# STM32F4.net
KiCad netlist of a schematic drawn in Altium Designer
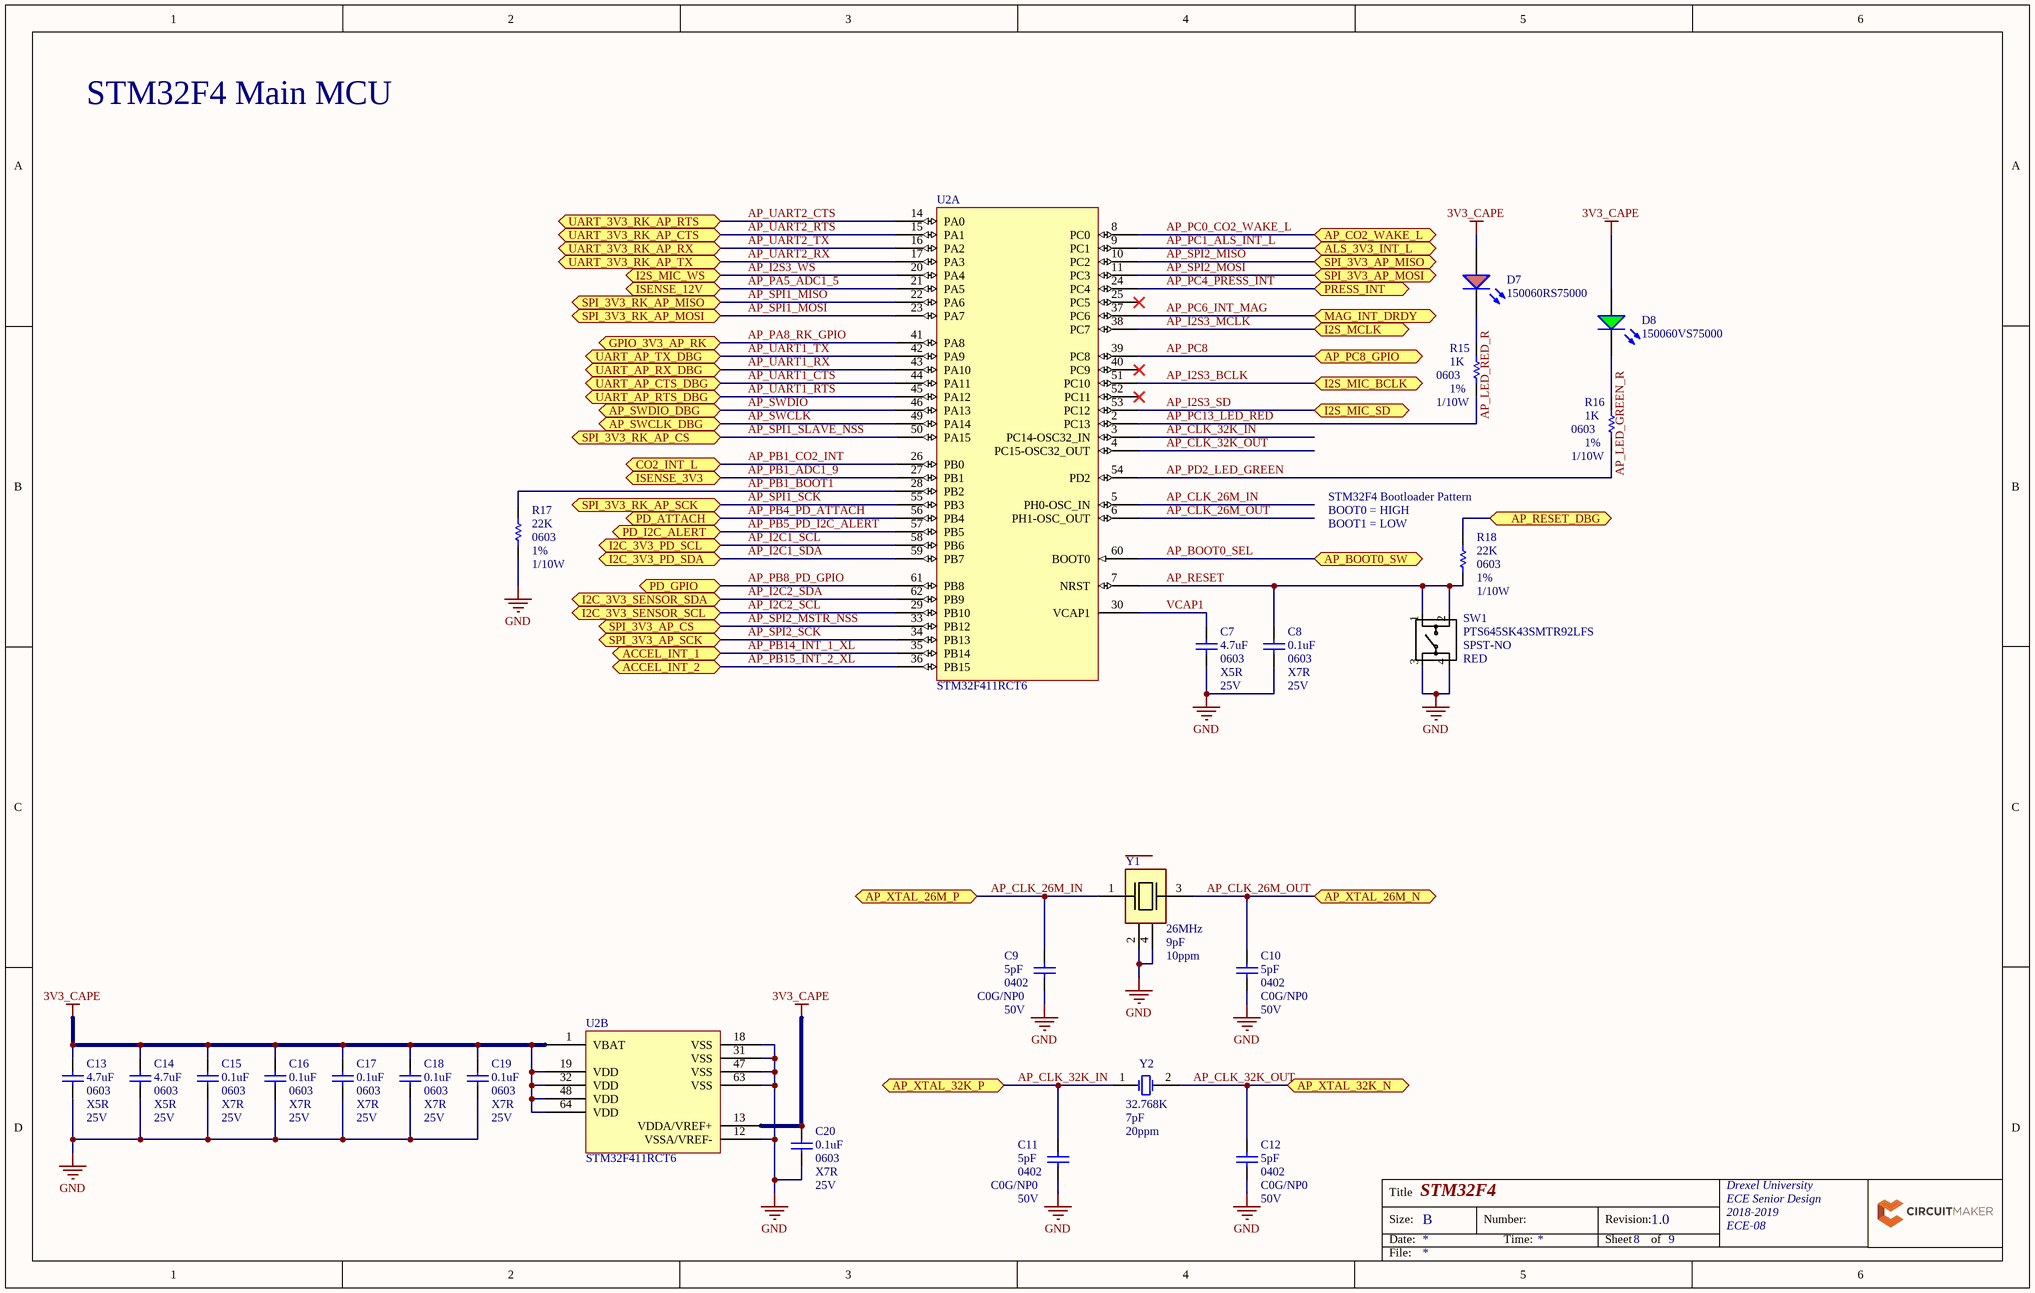
[diagram p0: STM32F4.SchDoc]

(export (version "E")
  (design (tool "Eeschema 10.0.6"))
  (components
    (comp (ref "C7")
      (value "Murata GRM188R61E475KE11D")
      (footprint "CAPC1608X90X35ML10T15")
      (description "CAP CER 4.7UF 25V 10% X5R 0603")
      (fields
        (field (name "CAPACITANCE") "4.7uF")
        (field (name "CASE/PACKAGE") "0603")
        (field (name "DIELECTRIC CHARACTERISTIC") "X5R")
        (field (name "VOLTAGE RATING (DC)") "25V")
        (field (name "MANUFACTURER PART NUMBER") "GRM188R61E475KE11D")
      )
      (libsource (lib "CommunityVault") (part "CMP-8856396-4"))
    )
    (comp (ref "C8")
      (value "Würth Elektronik 885012206071")
      (footprint "PCB-8usp83j76ntw2xroyu3n-1")
      (description "Multilayer Ceramic Capacitor, WCAP-CSGP Series, 0.1 F, 10%, X7R, 25 V, 0603 [1608 Metric]")
      (fields
        (field (name "DIELECTRIC CHARACTERISTIC") "X7R")
        (field (name "VOLTAGE RATING (DC)") "25V")
        (field (name "CAPACITANCE") "0.1uF")
        (field (name "MANUFACTURER PART NUMBER") "885012206071")
        (field (name "PACKAGE") "0603")
      )
      (libsource (lib "CommunityVault") (part "CMP-034ac9768ab0dc8d-1"))
    )
    (comp (ref "C9")
      (value "AVX Interconnect / Elco 04025A5R0CAT2A")
      (footprint "CAPC1005X56X25ML10T15")
      (description "Multilayer Ceramic Capacitors MLCC - SMD/SMT 0402 5pF 50volts C0G +/-0.25pF")
      (fields
        (field (name "CAPACITANCE") "5pF")
        (field (name "CASE/PACKAGE") "0402")
        (field (name "DIELECTRIC CHARACTERISTIC") "C0G/NP0")
        (field (name "VOLTAGE RATING (DC)") "50V")
        (field (name "MANUFACTURER PART NUMBER") "04025A5R0CAT2A")
      )
      (libsource (lib "CommunityVault") (part "CMP-173336-2"))
    )
    (comp (ref "C10")
      (value "AVX Interconnect / Elco 04025A5R0CAT2A")
      (footprint "CAPC1005X56X25ML10T15")
      (description "Multilayer Ceramic Capacitors MLCC - SMD/SMT 0402 5pF 50volts C0G +/-0.25pF")
      (fields
        (field (name "CAPACITANCE") "5pF")
        (field (name "CASE/PACKAGE") "0402")
        (field (name "DIELECTRIC CHARACTERISTIC") "C0G/NP0")
        (field (name "VOLTAGE RATING (DC)") "50V")
        (field (name "MANUFACTURER PART NUMBER") "04025A5R0CAT2A")
      )
      (libsource (lib "CommunityVault") (part "CMP-173336-2"))
    )
    (comp (ref "C11")
      (value "AVX Interconnect / Elco 04025A5R0CAT2A")
      (footprint "CAPC1005X56X25ML10T15")
      (description "Multilayer Ceramic Capacitors MLCC - SMD/SMT 0402 5pF 50volts C0G +/-0.25pF")
      (fields
        (field (name "CAPACITANCE") "5pF")
        (field (name "CASE/PACKAGE") "0402")
        (field (name "DIELECTRIC CHARACTERISTIC") "C0G/NP0")
        (field (name "VOLTAGE RATING (DC)") "50V")
        (field (name "MANUFACTURER PART NUMBER") "04025A5R0CAT2A")
      )
      (libsource (lib "CommunityVault") (part "CMP-173336-2"))
    )
    (comp (ref "C12")
      (value "AVX Interconnect / Elco 04025A5R0CAT2A")
      (footprint "CAPC1005X56X25ML10T15")
      (description "Multilayer Ceramic Capacitors MLCC - SMD/SMT 0402 5pF 50volts C0G +/-0.25pF")
      (fields
        (field (name "CAPACITANCE") "5pF")
        (field (name "CASE/PACKAGE") "0402")
        (field (name "DIELECTRIC CHARACTERISTIC") "C0G/NP0")
        (field (name "VOLTAGE RATING (DC)") "50V")
        (field (name "MANUFACTURER PART NUMBER") "04025A5R0CAT2A")
      )
      (libsource (lib "CommunityVault") (part "CMP-173336-2"))
    )
    (comp (ref "C13")
      (value "Murata GRM188R61E475KE11D")
      (footprint "CAPC1608X90X35ML10T15")
      (description "CAP CER 4.7UF 25V 10% X5R 0603")
      (fields
        (field (name "CAPACITANCE") "4.7uF")
        (field (name "CASE/PACKAGE") "0603")
        (field (name "DIELECTRIC CHARACTERISTIC") "X5R")
        (field (name "VOLTAGE RATING (DC)") "25V")
        (field (name "MANUFACTURER PART NUMBER") "GRM188R61E475KE11D")
      )
      (libsource (lib "CommunityVault") (part "CMP-8856396-4"))
    )
    (comp (ref "C14")
      (value "Murata GRM188R61E475KE11D")
      (footprint "CAPC1608X90X35ML10T15")
      (description "CAP CER 4.7UF 25V 10% X5R 0603")
      (fields
        (field (name "CAPACITANCE") "4.7uF")
        (field (name "CASE/PACKAGE") "0603")
        (field (name "DIELECTRIC CHARACTERISTIC") "X5R")
        (field (name "VOLTAGE RATING (DC)") "25V")
        (field (name "MANUFACTURER PART NUMBER") "GRM188R61E475KE11D")
      )
      (libsource (lib "CommunityVault") (part "CMP-8856396-4"))
    )
    (comp (ref "C15")
      (value "Würth Elektronik 885012206071")
      (footprint "PCB-8usp83j76ntw2xroyu3n-1")
      (description "Multilayer Ceramic Capacitor, WCAP-CSGP Series, 0.1 F, 10%, X7R, 25 V, 0603 [1608 Metric]")
      (fields
        (field (name "DIELECTRIC CHARACTERISTIC") "X7R")
        (field (name "VOLTAGE RATING (DC)") "25V")
        (field (name "CAPACITANCE") "0.1uF")
        (field (name "MANUFACTURER PART NUMBER") "885012206071")
        (field (name "PACKAGE") "0603")
      )
      (libsource (lib "CommunityVault") (part "CMP-034ac9768ab0dc8d-1"))
    )
    (comp (ref "C16")
      (value "Würth Elektronik 885012206071")
      (footprint "PCB-8usp83j76ntw2xroyu3n-1")
      (description "Multilayer Ceramic Capacitor, WCAP-CSGP Series, 0.1 F, 10%, X7R, 25 V, 0603 [1608 Metric]")
      (fields
        (field (name "DIELECTRIC CHARACTERISTIC") "X7R")
        (field (name "VOLTAGE RATING (DC)") "25V")
        (field (name "CAPACITANCE") "0.1uF")
        (field (name "MANUFACTURER PART NUMBER") "885012206071")
        (field (name "PACKAGE") "0603")
      )
      (libsource (lib "CommunityVault") (part "CMP-034ac9768ab0dc8d-1"))
    )
    (comp (ref "C17")
      (value "Würth Elektronik 885012206071")
      (footprint "PCB-8usp83j76ntw2xroyu3n-1")
      (description "Multilayer Ceramic Capacitor, WCAP-CSGP Series, 0.1 F, 10%, X7R, 25 V, 0603 [1608 Metric]")
      (fields
        (field (name "DIELECTRIC CHARACTERISTIC") "X7R")
        (field (name "VOLTAGE RATING (DC)") "25V")
        (field (name "CAPACITANCE") "0.1uF")
        (field (name "MANUFACTURER PART NUMBER") "885012206071")
        (field (name "PACKAGE") "0603")
      )
      (libsource (lib "CommunityVault") (part "CMP-034ac9768ab0dc8d-1"))
    )
    (comp (ref "C18")
      (value "Würth Elektronik 885012206071")
      (footprint "PCB-8usp83j76ntw2xroyu3n-1")
      (description "Multilayer Ceramic Capacitor, WCAP-CSGP Series, 0.1 F, 10%, X7R, 25 V, 0603 [1608 Metric]")
      (fields
        (field (name "DIELECTRIC CHARACTERISTIC") "X7R")
        (field (name "VOLTAGE RATING (DC)") "25V")
        (field (name "CAPACITANCE") "0.1uF")
        (field (name "MANUFACTURER PART NUMBER") "885012206071")
        (field (name "PACKAGE") "0603")
      )
      (libsource (lib "CommunityVault") (part "CMP-034ac9768ab0dc8d-1"))
    )
    (comp (ref "C19")
      (value "Würth Elektronik 885012206071")
      (footprint "PCB-8usp83j76ntw2xroyu3n-1")
      (description "Multilayer Ceramic Capacitor, WCAP-CSGP Series, 0.1 F, 10%, X7R, 25 V, 0603 [1608 Metric]")
      (fields
        (field (name "DIELECTRIC CHARACTERISTIC") "X7R")
        (field (name "VOLTAGE RATING (DC)") "25V")
        (field (name "CAPACITANCE") "0.1uF")
        (field (name "MANUFACTURER PART NUMBER") "885012206071")
        (field (name "PACKAGE") "0603")
      )
      (libsource (lib "CommunityVault") (part "CMP-034ac9768ab0dc8d-1"))
    )
    (comp (ref "C20")
      (value "Würth Elektronik 885012206071")
      (footprint "PCB-8usp83j76ntw2xroyu3n-1")
      (description "Multilayer Ceramic Capacitor, WCAP-CSGP Series, 0.1 F, 10%, X7R, 25 V, 0603 [1608 Metric]")
      (fields
        (field (name "DIELECTRIC CHARACTERISTIC") "X7R")
        (field (name "VOLTAGE RATING (DC)") "25V")
        (field (name "CAPACITANCE") "0.1uF")
        (field (name "MANUFACTURER PART NUMBER") "885012206071")
        (field (name "PACKAGE") "0603")
      )
      (libsource (lib "CommunityVault") (part "CMP-034ac9768ab0dc8d-1"))
    )
    (comp (ref "D7")
      (value "150060RS75000")
      (footprint "PCB-gaza7c7mdlgwi4y82xs2-1")
      (description "Standard LEDs - SMD WL-SMCW SMDMono TpVw Waterclr 0603 Red")
      (libsource (lib "CommunityVault") (part "SYM-47368ff9174098f1-2"))
    )
    (comp (ref "D8")
      (value "150060VS75000")
      (footprint "0603_A")
      (description "SMD mono-color Chip LED, WL-SMCW, Bright Green")
      (libsource (lib "FavoritesLibrary") (part "WE-LED_K1A2-2"))
    )
    (comp (ref "R15")
      (value "Stackpole Electronics RMCF0603FT1K00")
      (footprint "PCB-rzdzs5ckhrcob8ss0hvn-1")
      (description "RMCF Series 0603 0.1 W 1 kOhm ±1 % ±100 ppm/°C SMT Thick Film Chip Resistor")
      (fields
        (field (name "CASE/PACKAGE") "0603")
        (field (name "POWER RATING") "1/10W")
        (field (name "MANUFACTURER PART NUMBER") "RMCF0603FT1K00")
        (field (name "RESISTANCE") "1K")
        (field (name "RESISTANCE TOLERANCE") "1%")
      )
      (libsource (lib "CommunityVault") (part "CMP-fdb3359cf2042274-2"))
    )
    (comp (ref "R16")
      (value "Stackpole Electronics RMCF0603FT1K00")
      (footprint "PCB-rzdzs5ckhrcob8ss0hvn-1")
      (description "RMCF Series 0603 0.1 W 1 kOhm ±1 % ±100 ppm/°C SMT Thick Film Chip Resistor")
      (fields
        (field (name "CASE/PACKAGE") "0603")
        (field (name "POWER RATING") "1/10W")
        (field (name "MANUFACTURER PART NUMBER") "RMCF0603FT1K00")
        (field (name "RESISTANCE") "1K")
        (field (name "RESISTANCE TOLERANCE") "1%")
      )
      (libsource (lib "CommunityVault") (part "CMP-fdb3359cf2042274-2"))
    )
    (comp (ref "R17")
      (value "Yageo RC0603FR-0722KL")
      (footprint "RESC1608X55X25LL10T15")
      (description "Chip Resistor, 22 KOhm, +/- 1%, 0.1 W, -55 to 155 degC, 0603 (1608 Metric), RoHS, Tape and Reel")
      (fields
        (field (name "RESISTANCE") "22K")
        (field (name "RESISTANCE TOLERANCE") "1%")
        (field (name "CASE/PACKAGE") "0603")
        (field (name "POWER RATING") "1/10W")
        (field (name "MANUFACTURER PART NUMBER") "RC0603FR-0722KL")
      )
      (libsource (lib "CommunityVault") (part "CMP-1853446-5"))
    )
    (comp (ref "R18")
      (value "Yageo RC0603FR-0722KL")
      (footprint "RESC1608X55X25LL10T15")
      (description "Chip Resistor, 22 KOhm, +/- 1%, 0.1 W, -55 to 155 degC, 0603 (1608 Metric), RoHS, Tape and Reel")
      (fields
        (field (name "RESISTANCE") "22K")
        (field (name "RESISTANCE TOLERANCE") "1%")
        (field (name "CASE/PACKAGE") "0603")
        (field (name "POWER RATING") "1/10W")
        (field (name "MANUFACTURER PART NUMBER") "RC0603FR-0722KL")
      )
      (libsource (lib "CommunityVault") (part "CMP-1853446-5"))
    )
    (comp (ref "SW1")
      (value "C&K Components PTS645SK43SMTR92LFS")
      (footprint "PCB-2l25iuk5dcek232nr8ss-1")
      (description "Switch Tactile N.O SPST Round Button Gull Wing 0.05A 12VDC 100000Cycle 2.55N SMD T/R")
      (fields
        (field (name "MANUFACTURER PART NUMBER") "PTS645SK43SMTR92LFS")
        (field (name "CONTACTS TYPE") "SPST-NO")
      )
      (libsource (lib "CommunityVault") (part "CMP-8f9845df1015505f-1"))
    )
    (comp (ref "U2")
      (value "STM32F411RCT6")
      (footprint "STM32F411RCT6")
      (description "32 Bit Microcontroller, Batch Acquisition Mode, ARM Cortex-M4, 100 MHz, 256 KB, 128 KB, 64, LQFP")
      (libsource (lib "CommunityVault") (part "CMP-a3dd6807c7d17c1a-3"))
    )
    (comp (ref "Y1")
      (value "EPSON TSX-3225 26.0000MF09Z-AC0")
      (footprint "PCB-rtr9ii3g7ib08042rvg2-1")
      (description "Crystal 26.00 Mhz 9.0pf Smd")
      (fields
        (field (name "MANUFACTURER PART NUMBER") "TSX-3225 26.0000MF09Z-AC0")
        (field (name "FREQUENCY") "26MHz")
        (field (name "LOAD CAPACITANCE") "9pF")
        (field (name "TOLERANCE") "10ppm")
      )
      (libsource (lib "CommunityVault") (part "CMP-fc563492a5642391-2"))
    )
    (comp (ref "Y2")
      (value "SYM-533e9910b4df8cf9-1")
      (footprint "PCB-1zp5wd1v5813cd8flxka-1")
      (description "Crystal 0.032768MHz ±20ppm (Tol) 7pF FUND 70000Ohm 2-Pin SMD T/R")
      (fields
        (field (name "MANUFACTURER PART NUMBER") "FC-135 32.7680KA-AG0")
        (field (name "FREQUENCY") "32.768K")
        (field (name "LOAD CAPACITANCE") "7pF")
        (field (name "TOLERANCE") "20ppm")
      )
      (libsource (lib "CommunityVault") (part "CMP-533e9910b4df8cf9-1"))
    )
  )
  (nets
    (net (code "1") (name "/AP_BOOT0_SEL") (class "Default")
      (node (ref "U2") (pin "60") (pinfunction "BOOT0_60") (pintype "input"))
    )
    (net (code "2") (name "/AP_CLK_26M_IN") (class "Default")
      (node (ref "C9") (pin "2") (pinfunction "2_2") (pintype "passive"))
      (node (ref "U2") (pin "5") (pinfunction "PH0-OSC_IN_5") (pintype "bidirectional"))
      (node (ref "Y1") (pin "1") (pinfunction "X1_1") (pintype "passive"))
    )
    (net (code "3") (name "/AP_CLK_26M_OUT") (class "Default")
      (node (ref "C10") (pin "2") (pinfunction "2_2") (pintype "passive"))
      (node (ref "U2") (pin "6") (pinfunction "PH1-OSC_OUT_6") (pintype "bidirectional"))
      (node (ref "Y1") (pin "3") (pinfunction "X2_3") (pintype "passive"))
    )
    (net (code "4") (name "/AP_CLK_32K_IN") (class "Default")
      (node (ref "C11") (pin "2") (pinfunction "2_2") (pintype "passive"))
      (node (ref "U2") (pin "3") (pinfunction "PC14-OSC32_IN_3") (pintype "bidirectional"))
      (node (ref "Y2") (pin "1") (pinfunction "X1_1") (pintype "passive"))
    )
    (net (code "5") (name "/AP_CLK_32K_OUT") (class "Default")
      (node (ref "C12") (pin "2") (pinfunction "2_2") (pintype "passive"))
      (node (ref "U2") (pin "4") (pinfunction "PC15-OSC32_OUT_4") (pintype "bidirectional"))
      (node (ref "Y2") (pin "2") (pinfunction "X2_2") (pintype "passive"))
    )
    (net (code "6") (name "/AP_I2C1_SCL") (class "Default")
      (node (ref "U2") (pin "58") (pinfunction "PB6_58") (pintype "bidirectional"))
    )
    (net (code "7") (name "/AP_I2C1_SDA") (class "Default")
      (node (ref "U2") (pin "59") (pinfunction "PB7_59") (pintype "bidirectional"))
    )
    (net (code "8") (name "/AP_I2C2_SCL") (class "Default")
      (node (ref "U2") (pin "29") (pinfunction "PB10_29") (pintype "bidirectional"))
    )
    (net (code "9") (name "/AP_I2C2_SDA") (class "Default")
      (node (ref "U2") (pin "62") (pinfunction "PB9_62") (pintype "bidirectional"))
    )
    (net (code "10") (name "/AP_I2S3_BCLK") (class "Default")
      (node (ref "U2") (pin "51") (pinfunction "PC10_51") (pintype "bidirectional"))
    )
    (net (code "11") (name "/AP_I2S3_MCLK") (class "Default")
      (node (ref "U2") (pin "38") (pinfunction "PC7_38") (pintype "bidirectional"))
    )
    (net (code "12") (name "/AP_I2S3_SD") (class "Default")
      (node (ref "U2") (pin "53") (pinfunction "PC12_53") (pintype "bidirectional"))
    )
    (net (code "13") (name "/AP_I2S3_WS") (class "Default")
      (node (ref "U2") (pin "20") (pinfunction "PA4_20") (pintype "bidirectional"))
    )
    (net (code "14") (name "/AP_LED_GREEN_R") (class "Default")
      (node (ref "D8") (pin "1") (pinfunction "K_1") (pintype "passive"))
      (node (ref "R16") (pin "2") (pinfunction "2_2") (pintype "passive"))
    )
    (net (code "15") (name "/AP_LED_RED_R") (class "Default")
      (node (ref "D7") (pin "1") (pinfunction "K_1") (pintype "passive"))
      (node (ref "R15") (pin "2") (pinfunction "2_2") (pintype "passive"))
    )
    (net (code "16") (name "/AP_PA5_ADC1_5") (class "Default")
      (node (ref "U2") (pin "21") (pinfunction "PA5_21") (pintype "bidirectional"))
    )
    (net (code "17") (name "/AP_PA8_RK_GPIO") (class "Default")
      (node (ref "U2") (pin "41") (pinfunction "PA8_41") (pintype "bidirectional"))
    )
    (net (code "18") (name "/AP_PB1_ADC1_9") (class "Default")
      (node (ref "U2") (pin "27") (pinfunction "PB1_27") (pintype "bidirectional"))
    )
    (net (code "19") (name "/AP_PB1_BOOT1") (class "Default")
      (node (ref "R17") (pin "2") (pinfunction "2_2") (pintype "passive"))
      (node (ref "U2") (pin "28") (pinfunction "PB2_28") (pintype "bidirectional"))
    )
    (net (code "20") (name "/AP_PB1_CO2_INT") (class "Default")
      (node (ref "U2") (pin "26") (pinfunction "PB0_26") (pintype "bidirectional"))
    )
    (net (code "21") (name "/AP_PB4_PD_ATTACH") (class "Default")
      (node (ref "U2") (pin "56") (pinfunction "PB4_56") (pintype "bidirectional"))
    )
    (net (code "22") (name "/AP_PB5_PD_I2C_ALERT") (class "Default")
      (node (ref "U2") (pin "57") (pinfunction "PB5_57") (pintype "bidirectional"))
    )
    (net (code "23") (name "/AP_PB8_PD_GPIO") (class "Default")
      (node (ref "U2") (pin "61") (pinfunction "PB8_61") (pintype "bidirectional"))
    )
    (net (code "24") (name "/AP_PB14_INT_1_XL") (class "Default")
      (node (ref "U2") (pin "35") (pinfunction "PB14_35") (pintype "bidirectional"))
    )
    (net (code "25") (name "/AP_PB15_INT_2_XL") (class "Default")
      (node (ref "U2") (pin "36") (pinfunction "PB15_36") (pintype "bidirectional"))
    )
    (net (code "26") (name "/AP_PC0_CO2_WAKE_L") (class "Default")
      (node (ref "U2") (pin "8") (pinfunction "PC0_8") (pintype "bidirectional"))
    )
    (net (code "27") (name "/AP_PC1_ALS_INT_L") (class "Default")
      (node (ref "U2") (pin "9") (pinfunction "PC1_9") (pintype "bidirectional"))
    )
    (net (code "28") (name "/AP_PC4_PRESS_INT") (class "Default")
      (node (ref "U2") (pin "24") (pinfunction "PC4_24") (pintype "bidirectional"))
    )
    (net (code "29") (name "/AP_PC6_INT_MAG") (class "Default")
      (node (ref "U2") (pin "37") (pinfunction "PC6_37") (pintype "bidirectional"))
    )
    (net (code "30") (name "/AP_PC8") (class "Default")
      (node (ref "U2") (pin "39") (pinfunction "PC8_39") (pintype "bidirectional"))
    )
    (net (code "31") (name "/AP_PC13_LED_RED") (class "Default")
      (node (ref "R15") (pin "1") (pinfunction "1_1") (pintype "passive"))
      (node (ref "U2") (pin "2") (pinfunction "PC13_2") (pintype "bidirectional"))
    )
    (net (code "32") (name "/AP_PD2_LED_GREEN") (class "Default")
      (node (ref "R16") (pin "1") (pinfunction "1_1") (pintype "passive"))
      (node (ref "U2") (pin "54") (pinfunction "PD2_54") (pintype "bidirectional"))
    )
    (net (code "33") (name "/AP_RESET") (class "Default")
      (node (ref "C8") (pin "2") (pinfunction "2_2") (pintype "passive"))
      (node (ref "R18") (pin "1") (pinfunction "1_1") (pintype "passive"))
      (node (ref "SW1") (pin "1") (pinfunction "1_1") (pintype "passive"))
      (node (ref "SW1") (pin "2") (pinfunction "2_2") (pintype "passive"))
      (node (ref "U2") (pin "7") (pinfunction "NRST_7") (pintype "bidirectional"))
    )
    (net (code "34") (name "/AP_RESET_DBG") (class "Default")
      (node (ref "R18") (pin "2") (pinfunction "2_2") (pintype "passive"))
    )
    (net (code "35") (name "/AP_SPI1_MISO") (class "Default")
      (node (ref "U2") (pin "22") (pinfunction "PA6_22") (pintype "bidirectional"))
    )
    (net (code "36") (name "/AP_SPI1_MOSI") (class "Default")
      (node (ref "U2") (pin "23") (pinfunction "PA7_23") (pintype "bidirectional"))
    )
    (net (code "37") (name "/AP_SPI1_SCK") (class "Default")
      (node (ref "U2") (pin "55") (pinfunction "PB3_55") (pintype "bidirectional"))
    )
    (net (code "38") (name "/AP_SPI1_SLAVE_NSS") (class "Default")
      (node (ref "U2") (pin "50") (pinfunction "PA15_50") (pintype "bidirectional"))
    )
    (net (code "39") (name "/AP_SPI2_MISO") (class "Default")
      (node (ref "U2") (pin "10") (pinfunction "PC2_10") (pintype "bidirectional"))
    )
    (net (code "40") (name "/AP_SPI2_MOSI") (class "Default")
      (node (ref "U2") (pin "11") (pinfunction "PC3_11") (pintype "bidirectional"))
    )
    (net (code "41") (name "/AP_SPI2_MSTR_NSS") (class "Default")
      (node (ref "U2") (pin "33") (pinfunction "PB12_33") (pintype "bidirectional"))
    )
    (net (code "42") (name "/AP_SPI2_SCK") (class "Default")
      (node (ref "U2") (pin "34") (pinfunction "PB13_34") (pintype "bidirectional"))
    )
    (net (code "43") (name "/AP_SWCLK") (class "Default")
      (node (ref "U2") (pin "49") (pinfunction "PA14_49") (pintype "bidirectional"))
    )
    (net (code "44") (name "/AP_SWDIO") (class "Default")
      (node (ref "U2") (pin "46") (pinfunction "PA13_46") (pintype "bidirectional"))
    )
    (net (code "45") (name "/AP_UART1_CTS") (class "Default")
      (node (ref "U2") (pin "44") (pinfunction "PA11_44") (pintype "bidirectional"))
    )
    (net (code "46") (name "/AP_UART1_RTS") (class "Default")
      (node (ref "U2") (pin "45") (pinfunction "PA12_45") (pintype "bidirectional"))
    )
    (net (code "47") (name "/AP_UART1_RX") (class "Default")
      (node (ref "U2") (pin "43") (pinfunction "PA10_43") (pintype "bidirectional"))
    )
    (net (code "48") (name "/AP_UART1_TX") (class "Default")
      (node (ref "U2") (pin "42") (pinfunction "PA9_42") (pintype "bidirectional"))
    )
    (net (code "49") (name "/AP_UART2_CTS") (class "Default")
      (node (ref "U2") (pin "14") (pinfunction "PA0_14") (pintype "bidirectional"))
    )
    (net (code "50") (name "/AP_UART2_RTS") (class "Default")
      (node (ref "U2") (pin "15") (pinfunction "PA1_15") (pintype "bidirectional"))
    )
    (net (code "51") (name "/AP_UART2_RX") (class "Default")
      (node (ref "U2") (pin "17") (pinfunction "PA3_17") (pintype "bidirectional"))
    )
    (net (code "52") (name "/AP_UART2_TX") (class "Default")
      (node (ref "U2") (pin "16") (pinfunction "PA2_16") (pintype "bidirectional"))
    )
    (net (code "53") (name "/VCAP1") (class "Default")
      (node (ref "C7") (pin "2") (pinfunction "2_2") (pintype "passive"))
      (node (ref "U2") (pin "30") (pinfunction "VCAP1_30") (pintype "power_in"))
    )
    (net (code "54") (name "3V3_CAPE") (class "Default")
      (node (ref "C13") (pin "2") (pinfunction "2_2") (pintype "passive"))
      (node (ref "C14") (pin "2") (pinfunction "2_2") (pintype "passive"))
      (node (ref "C15") (pin "2") (pinfunction "2_2") (pintype "passive"))
      (node (ref "C16") (pin "2") (pinfunction "2_2") (pintype "passive"))
      (node (ref "C17") (pin "2") (pinfunction "2_2") (pintype "passive"))
      (node (ref "C18") (pin "2") (pinfunction "2_2") (pintype "passive"))
      (node (ref "C19") (pin "2") (pinfunction "2_2") (pintype "passive"))
      (node (ref "C20") (pin "2") (pinfunction "2_2") (pintype "passive"))
      (node (ref "D7") (pin "2") (pinfunction "A_2") (pintype "passive"))
      (node (ref "D8") (pin "2") (pinfunction "A_2") (pintype "passive"))
      (node (ref "U2") (pin "1") (pinfunction "VBAT_1") (pintype "power_in"))
      (node (ref "U2") (pin "13") (pinfunction "VDDA/VREF+_13") (pintype "power_in"))
      (node (ref "U2") (pin "19") (pinfunction "VDD_19") (pintype "power_in"))
      (node (ref "U2") (pin "32") (pinfunction "VDD_32") (pintype "power_in"))
      (node (ref "U2") (pin "48") (pinfunction "VDD_48") (pintype "power_in"))
      (node (ref "U2") (pin "64") (pinfunction "VDD_64") (pintype "power_in"))
    )
    (net (code "55") (name "GND") (class "Default")
      (node (ref "C10") (pin "1") (pinfunction "1_1") (pintype "passive"))
      (node (ref "C11") (pin "1") (pinfunction "1_1") (pintype "passive"))
      (node (ref "C12") (pin "1") (pinfunction "1_1") (pintype "passive"))
      (node (ref "C13") (pin "1") (pinfunction "1_1") (pintype "passive"))
      (node (ref "C14") (pin "1") (pinfunction "1_1") (pintype "passive"))
      (node (ref "C15") (pin "1") (pinfunction "1_1") (pintype "passive"))
      (node (ref "C16") (pin "1") (pinfunction "1_1") (pintype "passive"))
      (node (ref "C17") (pin "1") (pinfunction "1_1") (pintype "passive"))
      (node (ref "C18") (pin "1") (pinfunction "1_1") (pintype "passive"))
      (node (ref "C19") (pin "1") (pinfunction "1_1") (pintype "passive"))
      (node (ref "C20") (pin "1") (pinfunction "1_1") (pintype "passive"))
      (node (ref "C7") (pin "1") (pinfunction "1_1") (pintype "passive"))
      (node (ref "C8") (pin "1") (pinfunction "1_1") (pintype "passive"))
      (node (ref "C9") (pin "1") (pinfunction "1_1") (pintype "passive"))
      (node (ref "R17") (pin "1") (pinfunction "1_1") (pintype "passive"))
      (node (ref "SW1") (pin "3") (pinfunction "3_3") (pintype "passive"))
      (node (ref "SW1") (pin "4") (pinfunction "4_4") (pintype "passive"))
      (node (ref "U2") (pin "12") (pinfunction "VSSA/VREF-_12") (pintype "power_in"))
      (node (ref "U2") (pin "18") (pinfunction "VSS_18") (pintype "power_in"))
      (node (ref "U2") (pin "31") (pinfunction "VSS_31") (pintype "power_in"))
      (node (ref "U2") (pin "47") (pinfunction "VSS_47") (pintype "power_in"))
      (node (ref "U2") (pin "63") (pinfunction "VSS_63") (pintype "power_in"))
      (node (ref "Y1") (pin "2") (pinfunction "GND_2") (pintype "power_in"))
      (node (ref "Y1") (pin "4") (pinfunction "GND_4") (pintype "power_in"))
    )
    (net (code "56") (name "unconnected-(U2A-PC5-Pad25)") (class "Default")
      (node (ref "U2") (pin "25") (pinfunction "PC5_25") (pintype "bidirectional+no_connect"))
    )
    (net (code "57") (name "unconnected-(U2A-PC9-Pad40)") (class "Default")
      (node (ref "U2") (pin "40") (pinfunction "PC9_40") (pintype "bidirectional+no_connect"))
    )
    (net (code "58") (name "unconnected-(U2A-PC11-Pad52)") (class "Default")
      (node (ref "U2") (pin "52") (pinfunction "PC11_52") (pintype "bidirectional+no_connect"))
    )
  )
)
